# nigme1_Switch.net
KiCad netlist of a schematic drawn in Altium Designer
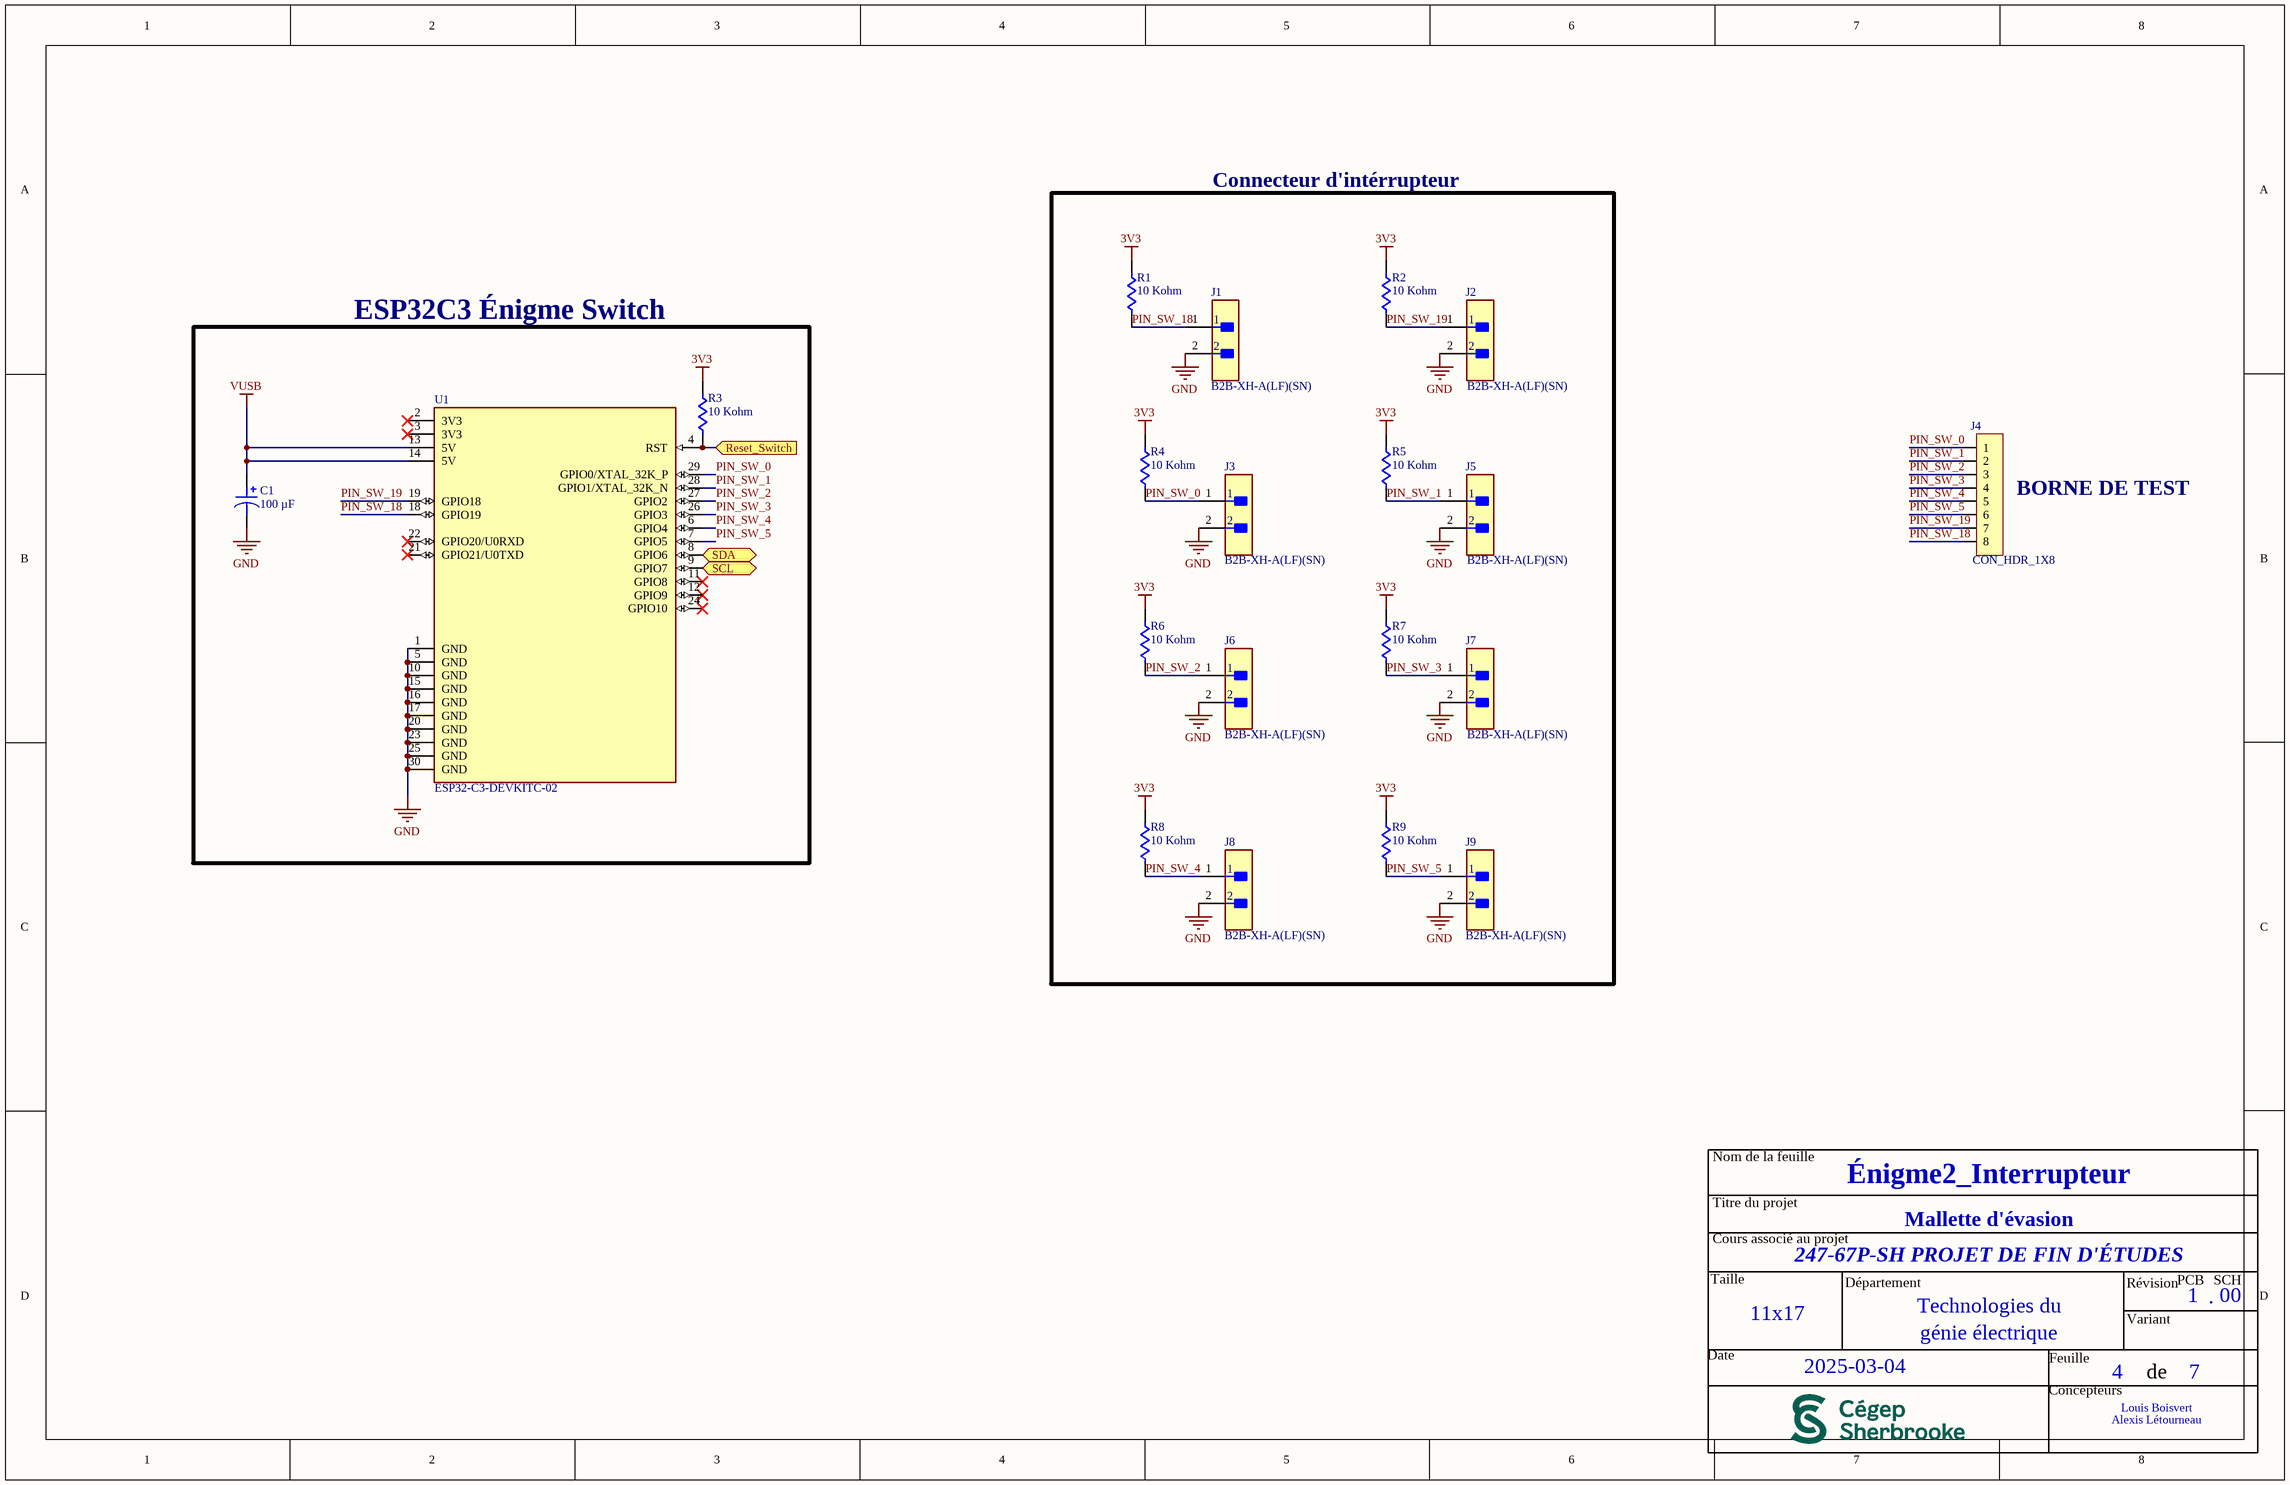
[diagram p0: Énigme1_Switch.SchDoc]

(export (version "E")
  (design (tool "Eeschema 10.0.6"))
  (components
    (comp (ref "C1")
      (value "100 µF")
      (footprint "CAP AL TH D8 L3.5 H12.5")
      (description "CAP ALUM 100UF 20% 50V RADIAL")
      (fields (field (name "PART NUMBER") "860020674015") (field (name "MANUFACTURER") "Würth Elektronik"))
      (libsource (lib "Celestial Altium Library - altium_library") (part "Polarised Capacitor"))
    )
    (comp (ref "J1")
      (value "B2B-XH-A(LF)(SN)")
      (footprint "FP-B2B-XH-A_LF_SN-MFG")
      (description "CONN HEADER VERT 2POS 2.5MM")
      (libsource (lib "Altium Content Vault") (part "3bc925449376181038e59eaffc5286c"))
    )
    (comp (ref "J2")
      (value "B2B-XH-A(LF)(SN)")
      (footprint "FP-B2B-XH-A_LF_SN-MFG")
      (description "CONN HEADER VERT 2POS 2.5MM")
      (libsource (lib "Altium Content Vault") (part "3bc925449376181038e59eaffc5286c"))
    )
    (comp (ref "J3")
      (value "B2B-XH-A(LF)(SN)")
      (footprint "FP-B2B-XH-A_LF_SN-MFG")
      (description "CONN HEADER VERT 2POS 2.5MM")
      (libsource (lib "Altium Content Vault") (part "3bc925449376181038e59eaffc5286c"))
    )
    (comp (ref "J4")
      (value "CON_HDR_1X8")
      (footprint "CON_HDR_1x8")
      (description "CON - Header 1X8 pins, 100Mils - TH-8")
      (fields (field (name "SOURCE") "CEGEP_SHERBROOKE_TGE_LIBRARY.SchLib"))
      (libsource (lib "Cegep de Sherbrooke") (part "CON_HDR_1X8"))
    )
    (comp (ref "J5")
      (value "B2B-XH-A(LF)(SN)")
      (footprint "FP-B2B-XH-A_LF_SN-MFG")
      (description "CONN HEADER VERT 2POS 2.5MM")
      (libsource (lib "Altium Content Vault") (part "3bc925449376181038e59eaffc5286c"))
    )
    (comp (ref "J6")
      (value "B2B-XH-A(LF)(SN)")
      (footprint "FP-B2B-XH-A_LF_SN-MFG")
      (description "CONN HEADER VERT 2POS 2.5MM")
      (libsource (lib "Altium Content Vault") (part "3bc925449376181038e59eaffc5286c"))
    )
    (comp (ref "J7")
      (value "B2B-XH-A(LF)(SN)")
      (footprint "FP-B2B-XH-A_LF_SN-MFG")
      (description "CONN HEADER VERT 2POS 2.5MM")
      (libsource (lib "Altium Content Vault") (part "3bc925449376181038e59eaffc5286c"))
    )
    (comp (ref "J8")
      (value "B2B-XH-A(LF)(SN)")
      (footprint "FP-B2B-XH-A_LF_SN-MFG")
      (description "CONN HEADER VERT 2POS 2.5MM")
      (libsource (lib "Altium Content Vault") (part "3bc925449376181038e59eaffc5286c"))
    )
    (comp (ref "J9")
      (value "B2B-XH-A(LF)(SN)")
      (footprint "FP-B2B-XH-A_LF_SN-MFG")
      (description "CONN HEADER VERT 2POS 2.5MM")
      (libsource (lib "Altium Content Vault") (part "3bc925449376181038e59eaffc5286c"))
    )
    (comp (ref "R1")
      (value "10 Kohm")
      (footprint "Res_Template")
      (description "Custom Semiconductor Resistor")
      (libsource (lib "Schlib1") (part "470 ohm"))
    )
    (comp (ref "R2")
      (value "10 Kohm")
      (footprint "Res_Template")
      (description "Custom Semiconductor Resistor")
      (libsource (lib "Schlib1") (part "470 ohm"))
    )
    (comp (ref "R3")
      (value "10 Kohm")
      (footprint "Res_Template")
      (description "Custom Semiconductor Resistor")
      (libsource (lib "Schlib1") (part "470 ohm"))
    )
    (comp (ref "R4")
      (value "10 Kohm")
      (footprint "Res_Template")
      (description "Custom Semiconductor Resistor")
      (libsource (lib "Schlib1") (part "470 ohm"))
    )
    (comp (ref "R5")
      (value "10 Kohm")
      (footprint "Res_Template")
      (description "Custom Semiconductor Resistor")
      (libsource (lib "Schlib1") (part "470 ohm"))
    )
    (comp (ref "R6")
      (value "10 Kohm")
      (footprint "Res_Template")
      (description "Custom Semiconductor Resistor")
      (libsource (lib "Schlib1") (part "470 ohm"))
    )
    (comp (ref "R7")
      (value "10 Kohm")
      (footprint "Res_Template")
      (description "Custom Semiconductor Resistor")
      (libsource (lib "Schlib1") (part "470 ohm"))
    )
    (comp (ref "R8")
      (value "10 Kohm")
      (footprint "Res_Template")
      (description "Custom Semiconductor Resistor")
      (libsource (lib "Schlib1") (part "470 ohm"))
    )
    (comp (ref "R9")
      (value "10 Kohm")
      (footprint "Res_Template")
      (description "Custom Semiconductor Resistor")
      (libsource (lib "Schlib1") (part "470 ohm"))
    )
    (comp (ref "U1")
      (value "ESP32-C3-DEVKITC-02")
      (footprint "XCVR_ESP32-C3-DEVKITC-02")
      (fields (field (name "MP") "ESP32-C3-DevKitC-02") (field (name "MF") "Espressif Systems"))
      (libsource (lib "ESP32-C3-DEVKITC-02") (part "ESP32-C3-DEVKITC-02"))
    )
  )
  (nets
    (net (code "1") (name "/PIN_SW_0") (class "Default")
      (node (ref "J3") (pin "1") (pinfunction "1_1") (pintype "passive"))
      (node (ref "J4") (pin "1") (pinfunction "1_1") (pintype "passive"))
      (node (ref "R4") (pin "1") (pinfunction "1_1") (pintype "passive"))
      (node (ref "U1") (pin "29") (pinfunction "GPIO0/XTAL_32K_P_29") (pintype "bidirectional"))
    )
    (net (code "2") (name "/PIN_SW_1") (class "Default")
      (node (ref "J4") (pin "2") (pinfunction "2_2") (pintype "passive"))
      (node (ref "J5") (pin "1") (pinfunction "1_1") (pintype "passive"))
      (node (ref "R5") (pin "1") (pinfunction "1_1") (pintype "passive"))
      (node (ref "U1") (pin "28") (pinfunction "GPIO1/XTAL_32K_N_28") (pintype "bidirectional"))
    )
    (net (code "3") (name "/PIN_SW_2") (class "Default")
      (node (ref "J4") (pin "3") (pinfunction "3_3") (pintype "passive"))
      (node (ref "J6") (pin "1") (pinfunction "1_1") (pintype "passive"))
      (node (ref "R6") (pin "1") (pinfunction "1_1") (pintype "passive"))
      (node (ref "U1") (pin "27") (pinfunction "GPIO2_27") (pintype "bidirectional"))
    )
    (net (code "4") (name "/PIN_SW_3") (class "Default")
      (node (ref "J4") (pin "4") (pinfunction "4_4") (pintype "passive"))
      (node (ref "J7") (pin "1") (pinfunction "1_1") (pintype "passive"))
      (node (ref "R7") (pin "1") (pinfunction "1_1") (pintype "passive"))
      (node (ref "U1") (pin "26") (pinfunction "GPIO3_26") (pintype "bidirectional"))
    )
    (net (code "5") (name "/PIN_SW_4") (class "Default")
      (node (ref "J4") (pin "5") (pinfunction "5_5") (pintype "passive"))
      (node (ref "J8") (pin "1") (pinfunction "1_1") (pintype "passive"))
      (node (ref "R8") (pin "1") (pinfunction "1_1") (pintype "passive"))
      (node (ref "U1") (pin "6") (pinfunction "GPIO4_6") (pintype "bidirectional"))
    )
    (net (code "6") (name "/PIN_SW_5") (class "Default")
      (node (ref "J4") (pin "6") (pinfunction "6_6") (pintype "passive"))
      (node (ref "J9") (pin "1") (pinfunction "1_1") (pintype "passive"))
      (node (ref "R9") (pin "1") (pinfunction "1_1") (pintype "passive"))
      (node (ref "U1") (pin "7") (pinfunction "GPIO5_7") (pintype "bidirectional"))
    )
    (net (code "7") (name "/PIN_SW_18") (class "Default")
      (node (ref "J1") (pin "1") (pinfunction "1_1") (pintype "passive"))
      (node (ref "J4") (pin "8") (pinfunction "8_8") (pintype "passive"))
      (node (ref "R1") (pin "1") (pinfunction "1_1") (pintype "passive"))
      (node (ref "U1") (pin "18") (pinfunction "GPIO19_18") (pintype "bidirectional"))
    )
    (net (code "8") (name "/PIN_SW_19") (class "Default")
      (node (ref "J2") (pin "1") (pinfunction "1_1") (pintype "passive"))
      (node (ref "J4") (pin "7") (pinfunction "7_7") (pintype "passive"))
      (node (ref "R2") (pin "1") (pinfunction "1_1") (pintype "passive"))
      (node (ref "U1") (pin "19") (pinfunction "GPIO18_19") (pintype "bidirectional"))
    )
    (net (code "9") (name "/Reset_Switch") (class "Default")
      (node (ref "R3") (pin "1") (pinfunction "1_1") (pintype "passive"))
      (node (ref "U1") (pin "4") (pinfunction "RST_4") (pintype "input"))
    )
    (net (code "10") (name "/SCL") (class "Default")
      (node (ref "U1") (pin "9") (pinfunction "GPIO7_9") (pintype "bidirectional"))
    )
    (net (code "11") (name "/SDA") (class "Default")
      (node (ref "U1") (pin "8") (pinfunction "GPIO6_8") (pintype "bidirectional"))
    )
    (net (code "12") (name "3V3") (class "Default")
      (node (ref "R1") (pin "2") (pinfunction "2_2") (pintype "passive"))
      (node (ref "R2") (pin "2") (pinfunction "2_2") (pintype "passive"))
      (node (ref "R3") (pin "2") (pinfunction "2_2") (pintype "passive"))
      (node (ref "R4") (pin "2") (pinfunction "2_2") (pintype "passive"))
      (node (ref "R5") (pin "2") (pinfunction "2_2") (pintype "passive"))
      (node (ref "R6") (pin "2") (pinfunction "2_2") (pintype "passive"))
      (node (ref "R7") (pin "2") (pinfunction "2_2") (pintype "passive"))
      (node (ref "R8") (pin "2") (pinfunction "2_2") (pintype "passive"))
      (node (ref "R9") (pin "2") (pinfunction "2_2") (pintype "passive"))
    )
    (net (code "13") (name "GND") (class "Default")
      (node (ref "C1") (pin "2") (pinfunction "2_2") (pintype "passive"))
      (node (ref "J1") (pin "2") (pinfunction "2_2") (pintype "passive"))
      (node (ref "J2") (pin "2") (pinfunction "2_2") (pintype "passive"))
      (node (ref "J3") (pin "2") (pinfunction "2_2") (pintype "passive"))
      (node (ref "J5") (pin "2") (pinfunction "2_2") (pintype "passive"))
      (node (ref "J6") (pin "2") (pinfunction "2_2") (pintype "passive"))
      (node (ref "J7") (pin "2") (pinfunction "2_2") (pintype "passive"))
      (node (ref "J8") (pin "2") (pinfunction "2_2") (pintype "passive"))
      (node (ref "J9") (pin "2") (pinfunction "2_2") (pintype "passive"))
      (node (ref "U1") (pin "1") (pinfunction "GND_1") (pintype "power_in"))
      (node (ref "U1") (pin "10") (pinfunction "GND_10") (pintype "power_in"))
      (node (ref "U1") (pin "15") (pinfunction "GND_15") (pintype "power_in"))
      (node (ref "U1") (pin "16") (pinfunction "GND_16") (pintype "power_in"))
      (node (ref "U1") (pin "17") (pinfunction "GND_17") (pintype "power_in"))
      (node (ref "U1") (pin "20") (pinfunction "GND_20") (pintype "power_in"))
      (node (ref "U1") (pin "23") (pinfunction "GND_23") (pintype "power_in"))
      (node (ref "U1") (pin "25") (pinfunction "GND_25") (pintype "power_in"))
      (node (ref "U1") (pin "30") (pinfunction "GND_30") (pintype "power_in"))
      (node (ref "U1") (pin "5") (pinfunction "GND_5") (pintype "power_in"))
    )
    (net (code "14") (name "VUSB") (class "Default")
      (node (ref "C1") (pin "1") (pinfunction "1_1") (pintype "passive"))
      (node (ref "U1") (pin "13") (pinfunction "5V_13") (pintype "power_in"))
      (node (ref "U1") (pin "14") (pinfunction "5V_14") (pintype "power_in"))
    )
    (net (code "15") (name "unconnected-(U1-3V3-Pad2)") (class "Default")
      (node (ref "U1") (pin "2") (pinfunction "3V3_2") (pintype "power_in+no_connect"))
    )
    (net (code "16") (name "unconnected-(U1-3V3-Pad3)") (class "Default")
      (node (ref "U1") (pin "3") (pinfunction "3V3_3") (pintype "power_in+no_connect"))
    )
    (net (code "17") (name "unconnected-(U1-GPIO8-Pad11)") (class "Default")
      (node (ref "U1") (pin "11") (pinfunction "GPIO8_11") (pintype "bidirectional+no_connect"))
    )
    (net (code "18") (name "unconnected-(U1-GPIO9-Pad12)") (class "Default")
      (node (ref "U1") (pin "12") (pinfunction "GPIO9_12") (pintype "bidirectional+no_connect"))
    )
    (net (code "19") (name "unconnected-(U1-GPIO10-Pad24)") (class "Default")
      (node (ref "U1") (pin "24") (pinfunction "GPIO10_24") (pintype "bidirectional+no_connect"))
    )
    (net (code "20") (name "unconnected-(U1-GPIO20{slash}U0RXD-Pad22)") (class "Default")
      (node (ref "U1") (pin "22") (pinfunction "GPIO20/U0RXD_22") (pintype "bidirectional+no_connect"))
    )
    (net (code "21") (name "unconnected-(U1-GPIO21{slash}U0TXD-Pad21)") (class "Default")
      (node (ref "U1") (pin "21") (pinfunction "GPIO21/U0TXD_21") (pintype "bidirectional+no_connect"))
    )
  )
)
